# gb_usb_programmer.net
KiCad netlist of a schematic drawn in EAGLE
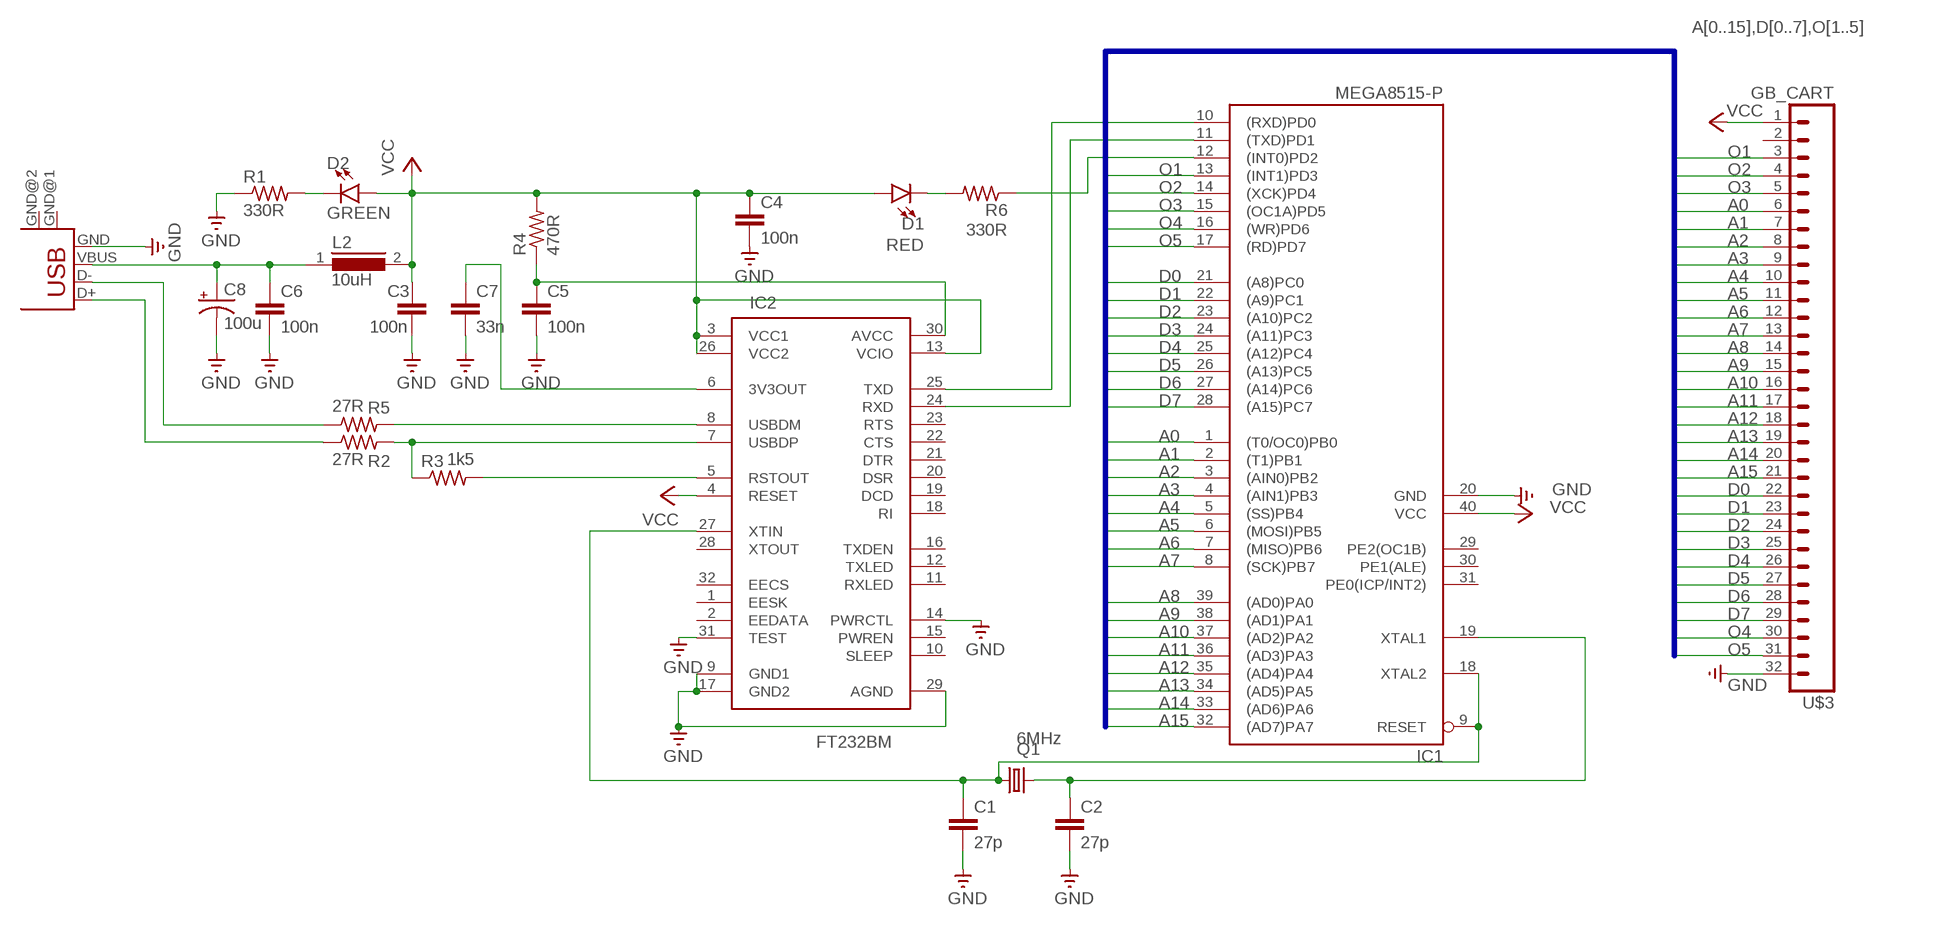
[diagram p0: schematic, sheet 1]

(export (version "E")
  (design (tool "Eeschema 10.0.6"))
  (components
    (comp (ref "C1")
      (value "27p")
      (footprint "eagle-import:C5B2.5")
      (libsource (lib "eagle-import") (part "C5/2.5"))
    )
    (comp (ref "C2")
      (value "27p")
      (footprint "eagle-import:C5B2.5")
      (libsource (lib "eagle-import") (part "C5/2.5"))
    )
    (comp (ref "C3")
      (value "100n")
      (footprint "eagle-import:C5B2.5")
      (libsource (lib "eagle-import") (part "C5/2.5"))
    )
    (comp (ref "C4")
      (value "100n")
      (footprint "eagle-import:C5B2.5")
      (libsource (lib "eagle-import") (part "C5/2.5"))
    )
    (comp (ref "C5")
      (value "100n")
      (footprint "eagle-import:C5B2.5")
      (libsource (lib "eagle-import") (part "C5/2.5"))
    )
    (comp (ref "C6")
      (value "100n")
      (footprint "eagle-import:C5B2.5")
      (libsource (lib "eagle-import") (part "C5/2.5"))
    )
    (comp (ref "C7")
      (value "33n")
      (footprint "eagle-import:C5B2.5")
      (libsource (lib "eagle-import") (part "C5/2.5"))
    )
    (comp (ref "C8")
      (value "100u")
      (footprint "eagle-import:E1,8-4")
      (libsource (lib "eagle-import") (part "CPOL-USE1.8-4"))
    )
    (comp (ref "D1")
      (value "RED")
      (footprint "eagle-import:LED_5MM-KIT")
      (libsource (lib "eagle-import") (part "LED5MM-KIT"))
    )
    (comp (ref "D2")
      (value "GREEN")
      (footprint "eagle-import:LED_5MM-KIT")
      (libsource (lib "eagle-import") (part "LED5MM-KIT"))
    )
    (comp (ref "IC1")
      (value "MEGA8515-P")
      (footprint "eagle-import:DIL40")
      (fields (field (name "MPN") "ATMEGA8515-16PU"))
      (libsource (lib "eagle-import") (part "MEGA8515-P"))
    )
    (comp (ref "IC2")
      (value "FT232BM")
      (footprint "eagle-import:QFP-32")
      (libsource (lib "eagle-import") (part "FT232BM"))
    )
    (comp (ref "L2")
      (value "10uH")
      (footprint "eagle-import:82114R")
      (libsource (lib "eagle-import") (part "82114R"))
    )
    (comp (ref "Q1")
      (value "6MHz")
      (footprint "eagle-import:HC49_S")
      (libsource (lib "eagle-import") (part "CRYSTALHC49S"))
    )
    (comp (ref "R1")
      (value "330R")
      (footprint "eagle-import:0207_10")
      (libsource (lib "eagle-import") (part "R-US_0207/10"))
    )
    (comp (ref "R2")
      (value "27R")
      (footprint "eagle-import:0207_10")
      (libsource (lib "eagle-import") (part "R-US_0207/10"))
    )
    (comp (ref "R3")
      (value "1k5")
      (footprint "eagle-import:0207_10")
      (libsource (lib "eagle-import") (part "R-US_0207/10"))
    )
    (comp (ref "R4")
      (value "470R")
      (footprint "eagle-import:0207_10")
      (libsource (lib "eagle-import") (part "R-US_0207/10"))
    )
    (comp (ref "R5")
      (value "27R")
      (footprint "eagle-import:0207_10")
      (libsource (lib "eagle-import") (part "R-US_0207/10"))
    )
    (comp (ref "R6")
      (value "330R")
      (footprint "eagle-import:0207_10")
      (libsource (lib "eagle-import") (part "R-US_0207/10"))
    )
    (comp (ref "U$3")
      (value "GB_CART")
      (footprint "eagle-import:1X32_GB")
      (libsource (lib "eagle-import") (part "M32GB"))
    )
    (comp (ref "USB1")
      (value "USB-B-H")
      (footprint "eagle-import:USB-B-H")
      (libsource (lib "eagle-import") (part "USB-B-H"))
    )
  )
  (nets
    (net (code "1") (name "/A0") (class "Default")
      (node (ref "IC1") (pin "1") (pinfunction "(T0/OC0)PB0_1") (pintype "bidirectional"))
      (node (ref "U$3") (pin "6") (pinfunction "6_6") (pintype "passive"))
    )
    (net (code "2") (name "/A1") (class "Default")
      (node (ref "IC1") (pin "2") (pinfunction "(T1)PB1_2") (pintype "bidirectional"))
      (node (ref "U$3") (pin "7") (pinfunction "7_7") (pintype "passive"))
    )
    (net (code "3") (name "/A2") (class "Default")
      (node (ref "IC1") (pin "3") (pinfunction "(AIN0)PB2_3") (pintype "bidirectional"))
      (node (ref "U$3") (pin "8") (pinfunction "8_8") (pintype "passive"))
    )
    (net (code "4") (name "/A3") (class "Default")
      (node (ref "IC1") (pin "4") (pinfunction "(AIN1)PB3_4") (pintype "bidirectional"))
      (node (ref "U$3") (pin "9") (pinfunction "9_9") (pintype "passive"))
    )
    (net (code "5") (name "/A4") (class "Default")
      (node (ref "IC1") (pin "5") (pinfunction "(SS)PB4_5") (pintype "bidirectional"))
      (node (ref "U$3") (pin "10") (pinfunction "10_10") (pintype "passive"))
    )
    (net (code "6") (name "/A5") (class "Default")
      (node (ref "IC1") (pin "6") (pinfunction "(MOSI)PB5_6") (pintype "bidirectional"))
      (node (ref "U$3") (pin "11") (pinfunction "11_11") (pintype "passive"))
    )
    (net (code "7") (name "/A6") (class "Default")
      (node (ref "IC1") (pin "7") (pinfunction "(MISO)PB6_7") (pintype "bidirectional"))
      (node (ref "U$3") (pin "12") (pinfunction "12_12") (pintype "passive"))
    )
    (net (code "8") (name "/A7") (class "Default")
      (node (ref "IC1") (pin "8") (pinfunction "(SCK)PB7_8") (pintype "bidirectional"))
      (node (ref "U$3") (pin "13") (pinfunction "13_13") (pintype "passive"))
    )
    (net (code "9") (name "/A8") (class "Default")
      (node (ref "IC1") (pin "39") (pinfunction "(AD0)PA0_39") (pintype "bidirectional"))
      (node (ref "U$3") (pin "14") (pinfunction "14_14") (pintype "passive"))
    )
    (net (code "10") (name "/A9") (class "Default")
      (node (ref "IC1") (pin "38") (pinfunction "(AD1)PA1_38") (pintype "bidirectional"))
      (node (ref "U$3") (pin "15") (pinfunction "15_15") (pintype "passive"))
    )
    (net (code "11") (name "/A10") (class "Default")
      (node (ref "IC1") (pin "37") (pinfunction "(AD2)PA2_37") (pintype "bidirectional"))
      (node (ref "U$3") (pin "16") (pinfunction "16_16") (pintype "passive"))
    )
    (net (code "12") (name "/A11") (class "Default")
      (node (ref "IC1") (pin "36") (pinfunction "(AD3)PA3_36") (pintype "bidirectional"))
      (node (ref "U$3") (pin "17") (pinfunction "17_17") (pintype "passive"))
    )
    (net (code "13") (name "/A12") (class "Default")
      (node (ref "IC1") (pin "35") (pinfunction "(AD4)PA4_35") (pintype "bidirectional"))
      (node (ref "U$3") (pin "18") (pinfunction "18_18") (pintype "passive"))
    )
    (net (code "14") (name "/A13") (class "Default")
      (node (ref "IC1") (pin "34") (pinfunction "(AD5)PA5_34") (pintype "bidirectional"))
      (node (ref "U$3") (pin "19") (pinfunction "19_19") (pintype "passive"))
    )
    (net (code "15") (name "/A14") (class "Default")
      (node (ref "IC1") (pin "33") (pinfunction "(AD6)PA6_33") (pintype "bidirectional"))
      (node (ref "U$3") (pin "20") (pinfunction "20_20") (pintype "passive"))
    )
    (net (code "16") (name "/A15") (class "Default")
      (node (ref "IC1") (pin "32") (pinfunction "(AD7)PA7_32") (pintype "bidirectional"))
      (node (ref "U$3") (pin "21") (pinfunction "21_21") (pintype "passive"))
    )
    (net (code "17") (name "/D0") (class "Default")
      (node (ref "IC1") (pin "21") (pinfunction "(A8)PC0_21") (pintype "bidirectional"))
      (node (ref "U$3") (pin "22") (pinfunction "22_22") (pintype "passive"))
    )
    (net (code "18") (name "/D1") (class "Default")
      (node (ref "IC1") (pin "22") (pinfunction "(A9)PC1_22") (pintype "bidirectional"))
      (node (ref "U$3") (pin "23") (pinfunction "23_23") (pintype "passive"))
    )
    (net (code "19") (name "/D2") (class "Default")
      (node (ref "IC1") (pin "23") (pinfunction "(A10)PC2_23") (pintype "bidirectional"))
      (node (ref "U$3") (pin "24") (pinfunction "24_24") (pintype "passive"))
    )
    (net (code "20") (name "/D3") (class "Default")
      (node (ref "IC1") (pin "24") (pinfunction "(A11)PC3_24") (pintype "bidirectional"))
      (node (ref "U$3") (pin "25") (pinfunction "25_25") (pintype "passive"))
    )
    (net (code "21") (name "/D4") (class "Default")
      (node (ref "IC1") (pin "25") (pinfunction "(A12)PC4_25") (pintype "bidirectional"))
      (node (ref "U$3") (pin "26") (pinfunction "26_26") (pintype "passive"))
    )
    (net (code "22") (name "/D5") (class "Default")
      (node (ref "IC1") (pin "26") (pinfunction "(A13)PC5_26") (pintype "bidirectional"))
      (node (ref "U$3") (pin "27") (pinfunction "27_27") (pintype "passive"))
    )
    (net (code "23") (name "/D6") (class "Default")
      (node (ref "IC1") (pin "27") (pinfunction "(A14)PC6_27") (pintype "bidirectional"))
      (node (ref "U$3") (pin "28") (pinfunction "28_28") (pintype "passive"))
    )
    (net (code "24") (name "/D7") (class "Default")
      (node (ref "IC1") (pin "28") (pinfunction "(A15)PC7_28") (pintype "bidirectional"))
      (node (ref "U$3") (pin "29") (pinfunction "29_29") (pintype "passive"))
    )
    (net (code "25") (name "/O1") (class "Default")
      (node (ref "IC1") (pin "13") (pinfunction "(INT1)PD3_13") (pintype "bidirectional"))
      (node (ref "U$3") (pin "3") (pinfunction "3_3") (pintype "passive"))
    )
    (net (code "26") (name "/O2") (class "Default")
      (node (ref "IC1") (pin "14") (pinfunction "(XCK)PD4_14") (pintype "bidirectional"))
      (node (ref "U$3") (pin "4") (pinfunction "4_4") (pintype "passive"))
    )
    (net (code "27") (name "/O3") (class "Default")
      (node (ref "IC1") (pin "15") (pinfunction "(OC1A)PD5_15") (pintype "bidirectional"))
      (node (ref "U$3") (pin "5") (pinfunction "5_5") (pintype "passive"))
    )
    (net (code "28") (name "/O4") (class "Default")
      (node (ref "IC1") (pin "16") (pinfunction "(WR)PD6_16") (pintype "bidirectional"))
      (node (ref "U$3") (pin "30") (pinfunction "30_30") (pintype "passive"))
    )
    (net (code "29") (name "/O5") (class "Default")
      (node (ref "IC1") (pin "17") (pinfunction "(RD)PD7_17") (pintype "bidirectional"))
      (node (ref "U$3") (pin "31") (pinfunction "31_31") (pintype "passive"))
    )
    (net (code "31") (name "GND") (class "Default")
      (node (ref "C1") (pin "2") (pinfunction "2_2") (pintype "passive"))
      (node (ref "C2") (pin "2") (pinfunction "2_2") (pintype "passive"))
      (node (ref "C3") (pin "2") (pinfunction "2_2") (pintype "passive"))
      (node (ref "C4") (pin "2") (pinfunction "2_2") (pintype "passive"))
      (node (ref "C5") (pin "2") (pinfunction "2_2") (pintype "passive"))
      (node (ref "C6") (pin "2") (pinfunction "2_2") (pintype "passive"))
      (node (ref "C7") (pin "2") (pinfunction "2_2") (pintype "passive"))
      (node (ref "C8") (pin "-") (pinfunction "-_-") (pintype "passive"))
      (node (ref "IC1") (pin "20") (pinfunction "GND_20") (pintype "power_in"))
      (node (ref "IC2") (pin "14") (pinfunction "PWRCTL_14") (pintype "input"))
      (node (ref "IC2") (pin "17") (pinfunction "GND2_17") (pintype "power_in"))
      (node (ref "IC2") (pin "29") (pinfunction "AGND_29") (pintype "input"))
      (node (ref "IC2") (pin "31") (pinfunction "TEST_31") (pintype "input"))
      (node (ref "IC2") (pin "9") (pinfunction "GND1_9") (pintype "power_in"))
      (node (ref "R1") (pin "1") (pinfunction "1_1") (pintype "passive"))
      (node (ref "U$3") (pin "32") (pinfunction "32_32") (pintype "passive"))
      (node (ref "USB1") (pin "GND") (pinfunction "GND_GND") (pintype "bidirectional"))
    )
    (net (code "32") (name "Net-(C6-Pad1)") (class "Default")
      (node (ref "C6") (pin "1") (pinfunction "1_1") (pintype "passive"))
      (node (ref "C8") (pin "+") (pinfunction "+_+") (pintype "passive"))
      (node (ref "L2") (pin "1") (pinfunction "1_1") (pintype "passive"))
      (node (ref "USB1") (pin "VBUS") (pinfunction "VBUS_VBUS") (pintype "bidirectional"))
    )
    (net (code "33") (name "Net-(D1-C)") (class "Default")
      (node (ref "D1") (pin "K") (pinfunction "C_K") (pintype "passive"))
      (node (ref "R6") (pin "2") (pinfunction "2_2") (pintype "passive"))
    )
    (net (code "34") (name "Net-(D2-C)") (class "Default")
      (node (ref "D2") (pin "K") (pinfunction "C_K") (pintype "passive"))
      (node (ref "R1") (pin "2") (pinfunction "2_2") (pintype "passive"))
    )
    (net (code "35") (name "Net-(IC1-(INT0)PD2)") (class "Default")
      (node (ref "IC1") (pin "12") (pinfunction "(INT0)PD2_12") (pintype "bidirectional"))
      (node (ref "R6") (pin "1") (pinfunction "1_1") (pintype "passive"))
    )
    (net (code "36") (name "Net-(IC1-(RXD)PD0)") (class "Default")
      (node (ref "IC1") (pin "10") (pinfunction "(RXD)PD0_10") (pintype "bidirectional"))
      (node (ref "IC2") (pin "25") (pinfunction "TXD_25") (pintype "output"))
    )
    (net (code "37") (name "Net-(IC1-(TXD)PD1)") (class "Default")
      (node (ref "IC1") (pin "11") (pinfunction "(TXD)PD1_11") (pintype "bidirectional"))
      (node (ref "IC2") (pin "24") (pinfunction "RXD_24") (pintype "input"))
    )
    (net (code "38") (name "Net-(IC1-RESET)") (class "Default")
      (node (ref "C1") (pin "1") (pinfunction "1_1") (pintype "passive"))
      (node (ref "IC1") (pin "18") (pinfunction "XTAL2_18") (pintype "bidirectional"))
      (node (ref "IC1") (pin "9") (pinfunction "RESET_9") (pintype "input"))
      (node (ref "IC2") (pin "27") (pinfunction "XTIN_27") (pintype "input"))
      (node (ref "Q1") (pin "1") (pinfunction "1_1") (pintype "passive"))
    )
    (net (code "39") (name "Net-(IC1-XTAL1)") (class "Default")
      (node (ref "C2") (pin "1") (pinfunction "1_1") (pintype "passive"))
      (node (ref "IC1") (pin "19") (pinfunction "XTAL1_19") (pintype "bidirectional"))
      (node (ref "Q1") (pin "2") (pinfunction "2_2") (pintype "passive"))
    )
    (net (code "40") (name "Net-(IC2-3V3OUT)") (class "Default")
      (node (ref "C7") (pin "1") (pinfunction "1_1") (pintype "passive"))
      (node (ref "IC2") (pin "6") (pinfunction "3V3OUT_6") (pintype "output"))
    )
    (net (code "41") (name "Net-(IC2-AVCC)") (class "Default")
      (node (ref "C5") (pin "1") (pinfunction "1_1") (pintype "passive"))
      (node (ref "IC2") (pin "30") (pinfunction "AVCC_30") (pintype "input"))
      (node (ref "R4") (pin "1") (pinfunction "1_1") (pintype "passive"))
    )
    (net (code "42") (name "Net-(IC2-RSTOUT)") (class "Default")
      (node (ref "IC2") (pin "5") (pinfunction "RSTOUT_5") (pintype "output"))
      (node (ref "R3") (pin "2") (pinfunction "2_2") (pintype "passive"))
    )
    (net (code "43") (name "Net-(IC2-USBDM)") (class "Default")
      (node (ref "IC2") (pin "8") (pinfunction "USBDM_8") (pintype "bidirectional"))
      (node (ref "R5") (pin "2") (pinfunction "2_2") (pintype "passive"))
    )
    (net (code "44") (name "Net-(IC2-USBDP)") (class "Default")
      (node (ref "IC2") (pin "7") (pinfunction "USBDP_7") (pintype "bidirectional"))
      (node (ref "R2") (pin "2") (pinfunction "2_2") (pintype "passive"))
      (node (ref "R3") (pin "1") (pinfunction "1_1") (pintype "passive"))
    )
    (net (code "45") (name "Net-(R2-Pad1)") (class "Default")
      (node (ref "R2") (pin "1") (pinfunction "1_1") (pintype "passive"))
      (node (ref "USB1") (pin "D+") (pinfunction "D+_D+") (pintype "bidirectional"))
    )
    (net (code "46") (name "Net-(R5-Pad1)") (class "Default")
      (node (ref "R5") (pin "1") (pinfunction "1_1") (pintype "passive"))
      (node (ref "USB1") (pin "D-") (pinfunction "D-_D-") (pintype "bidirectional"))
    )
    (net (code "47") (name "VCC") (class "Default")
      (node (ref "C3") (pin "1") (pinfunction "1_1") (pintype "passive"))
      (node (ref "C4") (pin "1") (pinfunction "1_1") (pintype "passive"))
      (node (ref "D1") (pin "A") (pinfunction "A_A") (pintype "passive"))
      (node (ref "D2") (pin "A") (pinfunction "A_A") (pintype "passive"))
      (node (ref "IC1") (pin "40") (pinfunction "VCC_40") (pintype "power_in"))
      (node (ref "IC2") (pin "13") (pinfunction "VCIO_13") (pintype "input"))
      (node (ref "IC2") (pin "26") (pinfunction "VCC2_26") (pintype "power_in"))
      (node (ref "IC2") (pin "3") (pinfunction "VCC1_3") (pintype "power_in"))
      (node (ref "IC2") (pin "4") (pinfunction "RESET_4") (pintype "input"))
      (node (ref "L2") (pin "2") (pinfunction "2_2") (pintype "passive"))
      (node (ref "R4") (pin "2") (pinfunction "2_2") (pintype "passive"))
      (node (ref "U$3") (pin "1") (pinfunction "1_1") (pintype "passive"))
    )
    (net (code "48") (name "unconnected-(IC1-PE0(ICP{slash}INT2)-Pad31)") (class "Default")
      (node (ref "IC1") (pin "31") (pinfunction "PE0(ICP/INT2)_31") (pintype "bidirectional"))
    )
    (net (code "49") (name "unconnected-(IC1-PE1(ALE)-Pad30)") (class "Default")
      (node (ref "IC1") (pin "30") (pinfunction "PE1(ALE)_30") (pintype "bidirectional"))
    )
    (net (code "50") (name "unconnected-(IC1-PE2(OC1B)-Pad29)") (class "Default")
      (node (ref "IC1") (pin "29") (pinfunction "PE2(OC1B)_29") (pintype "bidirectional"))
    )
    (net (code "51") (name "unconnected-(IC2-CTS-Pad22)") (class "Default")
      (node (ref "IC2") (pin "22") (pinfunction "CTS_22") (pintype "input"))
    )
    (net (code "52") (name "unconnected-(IC2-DCD-Pad19)") (class "Default")
      (node (ref "IC2") (pin "19") (pinfunction "DCD_19") (pintype "input"))
    )
    (net (code "53") (name "unconnected-(IC2-DSR-Pad20)") (class "Default")
      (node (ref "IC2") (pin "20") (pinfunction "DSR_20") (pintype "input"))
    )
    (net (code "54") (name "unconnected-(IC2-DTR-Pad21)") (class "Default")
      (node (ref "IC2") (pin "21") (pinfunction "DTR_21") (pintype "output"))
    )
    (net (code "55") (name "unconnected-(IC2-EECS-Pad32)") (class "Default")
      (node (ref "IC2") (pin "32") (pinfunction "EECS_32") (pintype "bidirectional"))
    )
    (net (code "56") (name "unconnected-(IC2-EEDATA-Pad2)") (class "Default")
      (node (ref "IC2") (pin "2") (pinfunction "EEDATA_2") (pintype "bidirectional"))
    )
    (net (code "57") (name "unconnected-(IC2-EESK-Pad1)") (class "Default")
      (node (ref "IC2") (pin "1") (pinfunction "EESK_1") (pintype "bidirectional"))
    )
    (net (code "58") (name "unconnected-(IC2-PWREN-Pad15)") (class "Default")
      (node (ref "IC2") (pin "15") (pinfunction "PWREN_15") (pintype "output"))
    )
    (net (code "59") (name "unconnected-(IC2-RI-Pad18)") (class "Default")
      (node (ref "IC2") (pin "18") (pinfunction "RI_18") (pintype "input"))
    )
    (net (code "60") (name "unconnected-(IC2-RTS-Pad23)") (class "Default")
      (node (ref "IC2") (pin "23") (pinfunction "RTS_23") (pintype "output"))
    )
    (net (code "61") (name "unconnected-(IC2-RXLED-Pad11)") (class "Default")
      (node (ref "IC2") (pin "11") (pinfunction "RXLED_11") (pintype "open_collector"))
    )
    (net (code "62") (name "unconnected-(IC2-SLEEP-Pad10)") (class "Default")
      (node (ref "IC2") (pin "10") (pinfunction "SLEEP_10") (pintype "output"))
    )
    (net (code "63") (name "unconnected-(IC2-TXDEN-Pad16)") (class "Default")
      (node (ref "IC2") (pin "16") (pinfunction "TXDEN_16") (pintype "output"))
    )
    (net (code "64") (name "unconnected-(IC2-TXLED-Pad12)") (class "Default")
      (node (ref "IC2") (pin "12") (pinfunction "TXLED_12") (pintype "open_collector"))
    )
    (net (code "65") (name "unconnected-(IC2-XTOUT-Pad28)") (class "Default")
      (node (ref "IC2") (pin "28") (pinfunction "XTOUT_28") (pintype "output"))
    )
    (net (code "66") (name "unconnected-(U$3-Pad2)") (class "Default")
      (node (ref "U$3") (pin "2") (pinfunction "2_2") (pintype "passive"))
    )
    (net (code "67") (name "unconnected-(USB1-GND-PadGND@1)") (class "Default")
      (node (ref "USB1") (pin "GND@1") (pinfunction "GND_GND@1") (pintype "bidirectional"))
    )
    (net (code "68") (name "unconnected-(USB1-GND-PadGND@2)") (class "Default")
      (node (ref "USB1") (pin "GND@2") (pinfunction "GND_GND@2") (pintype "bidirectional"))
    )
  )
)
